# v1.net
KiCad netlist of a schematic drawn in EAGLE
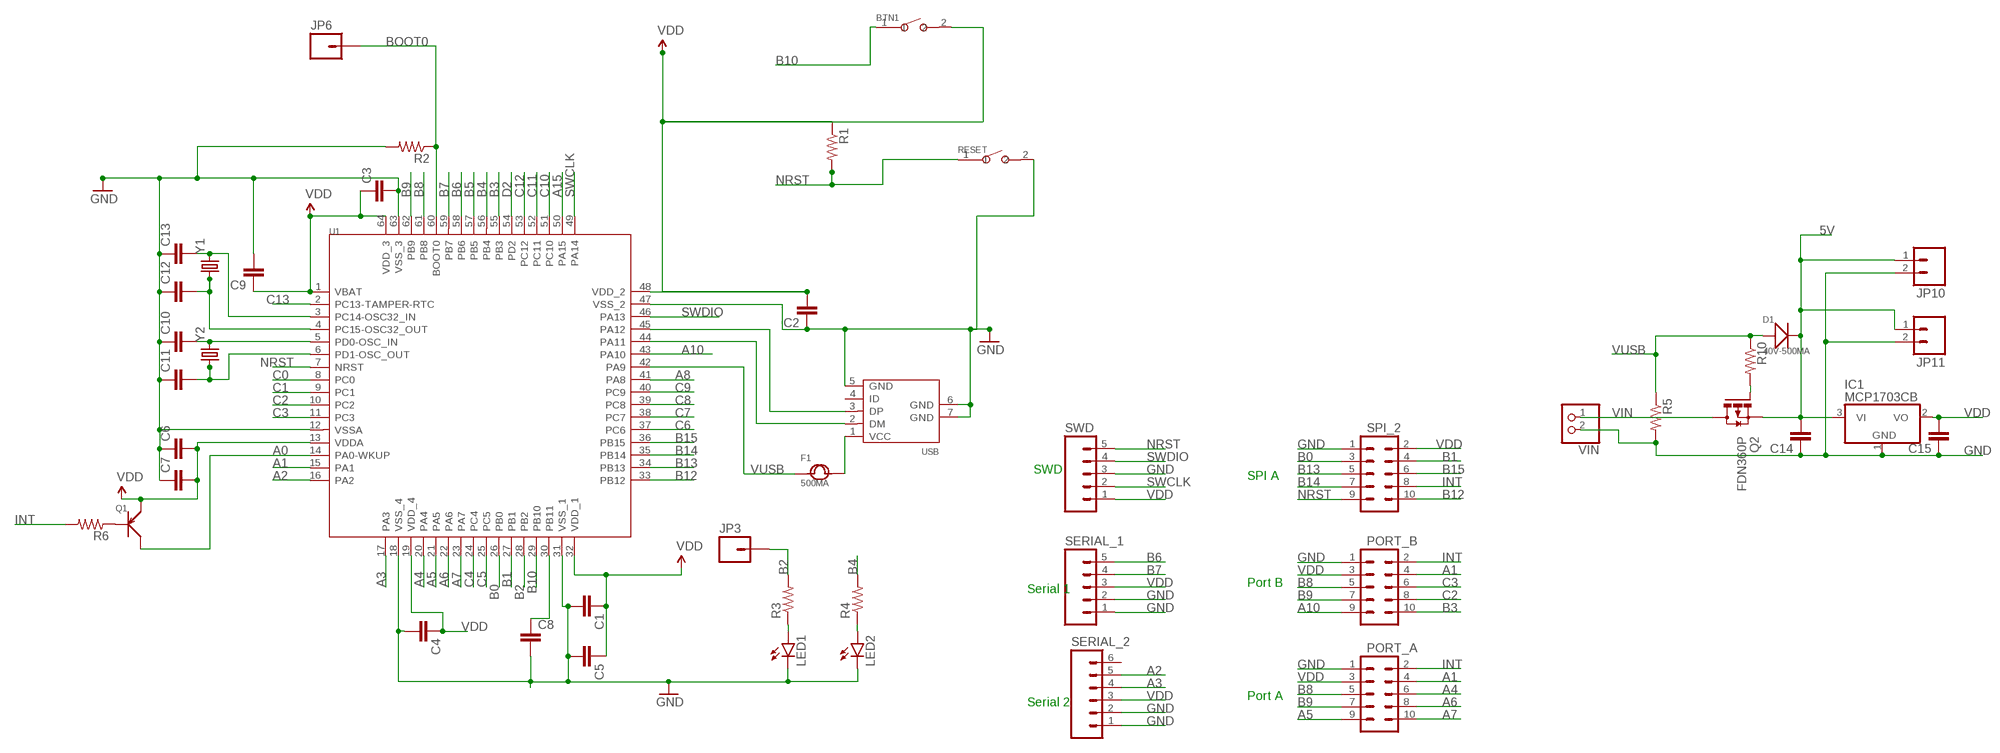
[diagram p0: schematic, sheet 1]

(export (version "E")
  (design (tool "Eeschema 10.0.6"))
  (components
    (comp (ref "BTN1")
      (value "SMD-BUTTON(2P-6.0X3.0X2.5MM)-DHT-1163S")
      (footprint "eagle-import:SW2-4.0-6.0X3.0X2.5MM")
      (libsource (lib "eagle-import") (part "SMD-BUTTON(2P-6.0X3.0X2.5MM)-DHT-1163S"))
    )
    (comp (ref "C1")
      (value "CAP0805")
      (footprint "eagle-import:0805")
      (libsource (lib "eagle-import") (part "CAP0805"))
    )
    (comp (ref "C2")
      (value "CAP0805")
      (footprint "eagle-import:0805")
      (libsource (lib "eagle-import") (part "CAP0805"))
    )
    (comp (ref "C3")
      (value "CAP0805")
      (footprint "eagle-import:0805")
      (libsource (lib "eagle-import") (part "CAP0805"))
    )
    (comp (ref "C4")
      (value "CAP0805")
      (footprint "eagle-import:0805")
      (libsource (lib "eagle-import") (part "CAP0805"))
    )
    (comp (ref "C5")
      (value "CAP0805")
      (footprint "eagle-import:0805")
      (libsource (lib "eagle-import") (part "CAP0805"))
    )
    (comp (ref "C6")
      (value "CAP0805")
      (footprint "eagle-import:0805")
      (libsource (lib "eagle-import") (part "CAP0805"))
    )
    (comp (ref "C7")
      (value "CAP0805")
      (footprint "eagle-import:0805")
      (libsource (lib "eagle-import") (part "CAP0805"))
    )
    (comp (ref "C8")
      (value "CAP0805")
      (footprint "eagle-import:0805")
      (libsource (lib "eagle-import") (part "CAP0805"))
    )
    (comp (ref "C9")
      (value "CAP0805")
      (footprint "eagle-import:0805")
      (libsource (lib "eagle-import") (part "CAP0805"))
    )
    (comp (ref "C10")
      (value "CAP0805")
      (footprint "eagle-import:0805")
      (libsource (lib "eagle-import") (part "CAP0805"))
    )
    (comp (ref "C11")
      (value "CAP0805")
      (footprint "eagle-import:0805")
      (libsource (lib "eagle-import") (part "CAP0805"))
    )
    (comp (ref "C12")
      (value "CAP0805")
      (footprint "eagle-import:0805")
      (libsource (lib "eagle-import") (part "CAP0805"))
    )
    (comp (ref "C13")
      (value "CAP0805")
      (footprint "eagle-import:0805")
      (libsource (lib "eagle-import") (part "CAP0805"))
    )
    (comp (ref "C14")
      (value "CAP0805")
      (footprint "eagle-import:0805")
      (libsource (lib "eagle-import") (part "CAP0805"))
    )
    (comp (ref "C15")
      (value "CAP0805")
      (footprint "eagle-import:0805")
      (libsource (lib "eagle-import") (part "CAP0805"))
    )
    (comp (ref "D1")
      (value "40V-500MA")
      (footprint "eagle-import:SOD-123")
      (fields (field (name "MPN") "B0540W"))
      (libsource (lib "eagle-import") (part "SMD-DIODE-SCHOTTKY-40V-500MA(SOD-123)"))
    )
    (comp (ref "F1")
      (value "500MA")
      (footprint "eagle-import:F1206")
      (libsource (lib "eagle-import") (part "SMD-PPTC-500MA(1206)"))
    )
    (comp (ref "IC1")
      (value "MCP1703CB")
      (footprint "eagle-import:SOT23")
      (libsource (lib "eagle-import") (part "MCP1703CB"))
    )
    (comp (ref "JP3")
      (value "M01NOSILK-KIT")
      (footprint "eagle-import:1X01NS-KIT")
      (libsource (lib "eagle-import") (part "M01NOSILK-KIT"))
    )
    (comp (ref "JP6")
      (value "M01NOSILK-KIT")
      (footprint "eagle-import:1X01NS-KIT")
      (libsource (lib "eagle-import") (part "M01NOSILK-KIT"))
    )
    (comp (ref "JP10")
      (value "M02PTH")
      (footprint "eagle-import:1X02")
      (libsource (lib "eagle-import") (part "M02PTH"))
    )
    (comp (ref "JP11")
      (value "M02PTH")
      (footprint "eagle-import:1X02")
      (libsource (lib "eagle-import") (part "M02PTH"))
    )
    (comp (ref "LED1")
      (value "LED1206")
      (footprint "eagle-import:LED-1206")
      (libsource (lib "eagle-import") (part "LED1206"))
    )
    (comp (ref "LED2")
      (value "LED1206")
      (footprint "eagle-import:LED-1206")
      (libsource (lib "eagle-import") (part "LED1206"))
    )
    (comp (ref "PORT_A")
      (value "M05X2PTH")
      (footprint "eagle-import:AVR_ICSP")
      (libsource (lib "eagle-import") (part "M05X2PTH"))
    )
    (comp (ref "PORT_B")
      (value "M05X2PTH")
      (footprint "eagle-import:AVR_ICSP")
      (libsource (lib "eagle-import") (part "M05X2PTH"))
    )
    (comp (ref "Q1")
      (value "SMD-TRANSISTORS-PNP-25V-500MA(SOT-23)")
      (footprint "eagle-import:SOT-23")
      (fields (field (name "MPN") "S8550"))
      (libsource (lib "eagle-import") (part "SMD-TRANSISTORS-PNP-25V-500MA(SOT-23)"))
    )
    (comp (ref "Q2")
      (value "FDN360P")
      (footprint "eagle-import:SUPER-SOT3")
      (libsource (lib "eagle-import") (part "FDN360P"))
    )
    (comp (ref "R1")
      (value "RESISTOR0805-RES")
      (footprint "eagle-import:0805")
      (libsource (lib "eagle-import") (part "RESISTOR0805-RES"))
    )
    (comp (ref "R2")
      (value "RESISTOR0805-RES")
      (footprint "eagle-import:0805")
      (libsource (lib "eagle-import") (part "RESISTOR0805-RES"))
    )
    (comp (ref "R3")
      (value "RESISTOR0805-RES")
      (footprint "eagle-import:0805")
      (libsource (lib "eagle-import") (part "RESISTOR0805-RES"))
    )
    (comp (ref "R4")
      (value "RESISTOR0805-RES")
      (footprint "eagle-import:0805")
      (libsource (lib "eagle-import") (part "RESISTOR0805-RES"))
    )
    (comp (ref "R5")
      (value "RESISTOR0805-RES")
      (footprint "eagle-import:0805")
      (libsource (lib "eagle-import") (part "RESISTOR0805-RES"))
    )
    (comp (ref "R6")
      (value "RESISTOR0805-RES")
      (footprint "eagle-import:0805")
      (libsource (lib "eagle-import") (part "RESISTOR0805-RES"))
    )
    (comp (ref "R10")
      (value "RESISTOR0805-RES")
      (footprint "eagle-import:0805")
      (libsource (lib "eagle-import") (part "RESISTOR0805-RES"))
    )
    (comp (ref "RESET")
      (value "SMD-BUTTON(2P-6.0X3.0X2.5MM)-DHT-1163S")
      (footprint "eagle-import:SW2-4.0-6.0X3.0X2.5MM")
      (libsource (lib "eagle-import") (part "SMD-BUTTON(2P-6.0X3.0X2.5MM)-DHT-1163S"))
    )
    (comp (ref "SERIAL_1")
      (value "M051.27MM")
      (footprint "eagle-import:1X05-1.27MM")
      (libsource (lib "eagle-import") (part "M051.27MM"))
    )
    (comp (ref "SERIAL_2")
      (value "M06SILK_FEMALE_PTH")
      (footprint "eagle-import:1X06")
      (libsource (lib "eagle-import") (part "M06SILK_FEMALE_PTH"))
    )
    (comp (ref "SPI_2")
      (value "M05X2PTH")
      (footprint "eagle-import:AVR_ICSP")
      (libsource (lib "eagle-import") (part "M05X2PTH"))
    )
    (comp (ref "SWD")
      (value "M051.27MM")
      (footprint "eagle-import:1X05-1.27MM")
      (libsource (lib "eagle-import") (part "M051.27MM"))
    )
    (comp (ref "U1")
      (value "MCU-STM32F401RBT6(LQFP64)")
      (footprint "eagle-import:LQFP64-0.5-10X10MM")
      (fields (field (name "MPN") "STM32F401RBT6"))
      (libsource (lib "eagle-import") (part "MCU-STM32F401RBT6(LQFP64)"))
    )
    (comp (ref "USB")
      (value "MICRO-USB-SMD-TYPE-AB-R/A(ST-USB-001L)")
      (footprint "eagle-import:MICRO-USB5+2P-SMD-0.65")
      (fields (field (name "MPN") "ST-USB-001L"))
      (libsource (lib "eagle-import") (part "MICRO-USB-SMD-TYPE-AB-R/A(ST-USB-001L)"))
    )
    (comp (ref "VIN")
      (value "JST_2PIN-SMT-RA")
      (footprint "eagle-import:JST-PH-2-SMT-RA")
      (libsource (lib "eagle-import") (part "JST_2PIN-SMT-RA"))
    )
    (comp (ref "Y1")
      (value "CRYSTAL5X3")
      (footprint "eagle-import:CRYSTAL-SMD-5X3")
      (libsource (lib "eagle-import") (part "CRYSTAL5X3"))
    )
    (comp (ref "Y2")
      (value "CRYSTAL5X3")
      (footprint "eagle-import:CRYSTAL-SMD-5X3")
      (libsource (lib "eagle-import") (part "CRYSTAL5X3"))
    )
  )
  (nets
    (net (code "1") (name "/5V") (class "Default")
      (node (ref "C14") (pin "2") (pinfunction "2_2") (pintype "passive"))
      (node (ref "D1") (pin "-") (pinfunction "-_-") (pintype "passive"))
      (node (ref "IC1") (pin "3") (pinfunction "VI_3") (pintype "input"))
      (node (ref "JP10") (pin "1") (pinfunction "1_1") (pintype "passive"))
      (node (ref "JP11") (pin "1") (pinfunction "1_1") (pintype "passive"))
      (node (ref "Q2") (pin "2") (pinfunction "S_2") (pintype "passive"))
    )
    (net (code "2") (name "/A0") (class "Default")
      (node (ref "Q1") (pin "3") (pinfunction "C_3") (pintype "passive"))
      (node (ref "U1") (pin "14") (pinfunction "PA0-WKUP_14") (pintype "bidirectional"))
    )
    (net (code "3") (name "/A1") (class "Default")
      (node (ref "PORT_A") (pin "4") (pinfunction "4_4") (pintype "passive"))
      (node (ref "PORT_B") (pin "4") (pinfunction "4_4") (pintype "passive"))
      (node (ref "U1") (pin "15") (pinfunction "PA1_15") (pintype "bidirectional"))
    )
    (net (code "4") (name "/A2") (class "Default")
      (node (ref "SERIAL_2") (pin "5") (pinfunction "5_5") (pintype "passive"))
      (node (ref "U1") (pin "16") (pinfunction "PA2_16") (pintype "bidirectional"))
    )
    (net (code "5") (name "/A3") (class "Default")
      (node (ref "SERIAL_2") (pin "4") (pinfunction "4_4") (pintype "passive"))
      (node (ref "U1") (pin "17") (pinfunction "PA3_17") (pintype "bidirectional"))
    )
    (net (code "6") (name "/A4") (class "Default")
      (node (ref "PORT_A") (pin "6") (pinfunction "6_6") (pintype "passive"))
      (node (ref "U1") (pin "20") (pinfunction "PA4_20") (pintype "bidirectional"))
    )
    (net (code "7") (name "/A5") (class "Default")
      (node (ref "PORT_A") (pin "9") (pinfunction "9_9") (pintype "passive"))
      (node (ref "U1") (pin "21") (pinfunction "PA5_21") (pintype "bidirectional"))
    )
    (net (code "8") (name "/A6") (class "Default")
      (node (ref "PORT_A") (pin "8") (pinfunction "8_8") (pintype "passive"))
      (node (ref "U1") (pin "22") (pinfunction "PA6_22") (pintype "bidirectional"))
    )
    (net (code "9") (name "/A7") (class "Default")
      (node (ref "PORT_A") (pin "10") (pinfunction "10_10") (pintype "passive"))
      (node (ref "U1") (pin "23") (pinfunction "PA7_23") (pintype "bidirectional"))
    )
    (net (code "10") (name "/A8") (class "Default")
      (node (ref "U1") (pin "41") (pinfunction "PA8_41") (pintype "bidirectional"))
    )
    (net (code "11") (name "/A10") (class "Default")
      (node (ref "PORT_B") (pin "9") (pinfunction "9_9") (pintype "passive"))
      (node (ref "U1") (pin "43") (pinfunction "PA10_43") (pintype "bidirectional"))
    )
    (net (code "12") (name "/A15") (class "Default")
      (node (ref "U1") (pin "50") (pinfunction "PA15_50") (pintype "bidirectional"))
    )
    (net (code "13") (name "/B0") (class "Default")
      (node (ref "SPI_2") (pin "3") (pinfunction "3_3") (pintype "passive"))
      (node (ref "U1") (pin "26") (pinfunction "PB0_26") (pintype "bidirectional"))
    )
    (net (code "14") (name "/B1") (class "Default")
      (node (ref "SPI_2") (pin "4") (pinfunction "4_4") (pintype "passive"))
      (node (ref "U1") (pin "27") (pinfunction "PB1_27") (pintype "bidirectional"))
    )
    (net (code "15") (name "/B2") (class "Default")
      (node (ref "JP3") (pin "1") (pinfunction "1_1") (pintype "passive"))
      (node (ref "R3") (pin "2") (pinfunction "2_2") (pintype "passive"))
      (node (ref "U1") (pin "28") (pinfunction "PB2_28") (pintype "bidirectional"))
    )
    (net (code "16") (name "/B3") (class "Default")
      (node (ref "PORT_B") (pin "10") (pinfunction "10_10") (pintype "passive"))
      (node (ref "U1") (pin "55") (pinfunction "PB3_55") (pintype "bidirectional"))
    )
    (net (code "17") (name "/B4") (class "Default")
      (node (ref "R4") (pin "2") (pinfunction "2_2") (pintype "passive"))
      (node (ref "U1") (pin "56") (pinfunction "PB4_56") (pintype "bidirectional"))
    )
    (net (code "18") (name "/B5") (class "Default")
      (node (ref "U1") (pin "57") (pinfunction "PB5_57") (pintype "bidirectional"))
    )
    (net (code "19") (name "/B6") (class "Default")
      (node (ref "SERIAL_1") (pin "5") (pinfunction "5_5") (pintype "passive"))
      (node (ref "U1") (pin "58") (pinfunction "PB6_58") (pintype "bidirectional"))
    )
    (net (code "20") (name "/B7") (class "Default")
      (node (ref "SERIAL_1") (pin "4") (pinfunction "4_4") (pintype "passive"))
      (node (ref "U1") (pin "59") (pinfunction "PB7_59") (pintype "bidirectional"))
    )
    (net (code "21") (name "/B8") (class "Default")
      (node (ref "PORT_A") (pin "5") (pinfunction "5_5") (pintype "passive"))
      (node (ref "PORT_B") (pin "5") (pinfunction "5_5") (pintype "passive"))
      (node (ref "U1") (pin "61") (pinfunction "PB8_61") (pintype "bidirectional"))
    )
    (net (code "22") (name "/B9") (class "Default")
      (node (ref "PORT_A") (pin "7") (pinfunction "7_7") (pintype "passive"))
      (node (ref "PORT_B") (pin "7") (pinfunction "7_7") (pintype "passive"))
      (node (ref "U1") (pin "62") (pinfunction "PB9_62") (pintype "bidirectional"))
    )
    (net (code "23") (name "/B10") (class "Default")
      (node (ref "BTN1") (pin "1") (pinfunction "1_1") (pintype "bidirectional"))
      (node (ref "U1") (pin "29") (pinfunction "PB10_29") (pintype "bidirectional"))
    )
    (net (code "24") (name "/B12") (class "Default")
      (node (ref "SPI_2") (pin "10") (pinfunction "10_10") (pintype "passive"))
      (node (ref "U1") (pin "33") (pinfunction "PB12_33") (pintype "bidirectional"))
    )
    (net (code "25") (name "/B13") (class "Default")
      (node (ref "SPI_2") (pin "5") (pinfunction "5_5") (pintype "passive"))
      (node (ref "U1") (pin "34") (pinfunction "PB13_34") (pintype "bidirectional"))
    )
    (net (code "26") (name "/B14") (class "Default")
      (node (ref "SPI_2") (pin "7") (pinfunction "7_7") (pintype "passive"))
      (node (ref "U1") (pin "35") (pinfunction "PB14_35") (pintype "bidirectional"))
    )
    (net (code "27") (name "/B15") (class "Default")
      (node (ref "SPI_2") (pin "6") (pinfunction "6_6") (pintype "passive"))
      (node (ref "U1") (pin "36") (pinfunction "PB15_36") (pintype "bidirectional"))
    )
    (net (code "28") (name "/BOOT0") (class "Default")
      (node (ref "JP6") (pin "1") (pinfunction "1_1") (pintype "passive"))
      (node (ref "R2") (pin "1") (pinfunction "1_1") (pintype "passive"))
      (node (ref "U1") (pin "60") (pinfunction "BOOT0_60") (pintype "bidirectional"))
    )
    (net (code "29") (name "/C0") (class "Default")
      (node (ref "U1") (pin "8") (pinfunction "PC0_8") (pintype "bidirectional"))
    )
    (net (code "30") (name "/C1") (class "Default")
      (node (ref "U1") (pin "9") (pinfunction "PC1_9") (pintype "bidirectional"))
    )
    (net (code "31") (name "/C2") (class "Default")
      (node (ref "PORT_B") (pin "8") (pinfunction "8_8") (pintype "passive"))
      (node (ref "U1") (pin "10") (pinfunction "PC2_10") (pintype "bidirectional"))
    )
    (net (code "32") (name "/C3") (class "Default")
      (node (ref "PORT_B") (pin "6") (pinfunction "6_6") (pintype "passive"))
      (node (ref "U1") (pin "11") (pinfunction "PC3_11") (pintype "bidirectional"))
    )
    (net (code "33") (name "/C4") (class "Default")
      (node (ref "U1") (pin "24") (pinfunction "PC4_24") (pintype "bidirectional"))
    )
    (net (code "34") (name "/C5") (class "Default")
      (node (ref "U1") (pin "25") (pinfunction "PC5_25") (pintype "bidirectional"))
    )
    (net (code "35") (name "/C6") (class "Default")
      (node (ref "U1") (pin "37") (pinfunction "PC6_37") (pintype "bidirectional"))
    )
    (net (code "36") (name "/C7") (class "Default")
      (node (ref "U1") (pin "38") (pinfunction "PC7_38") (pintype "bidirectional"))
    )
    (net (code "37") (name "/C8") (class "Default")
      (node (ref "U1") (pin "39") (pinfunction "PC8_39") (pintype "bidirectional"))
    )
    (net (code "38") (name "/C9") (class "Default")
      (node (ref "U1") (pin "40") (pinfunction "PC9_40") (pintype "bidirectional"))
    )
    (net (code "39") (name "/C10") (class "Default")
      (node (ref "U1") (pin "51") (pinfunction "PC10_51") (pintype "bidirectional"))
    )
    (net (code "40") (name "/C11") (class "Default")
      (node (ref "U1") (pin "52") (pinfunction "PC11_52") (pintype "bidirectional"))
    )
    (net (code "41") (name "/C12") (class "Default")
      (node (ref "U1") (pin "53") (pinfunction "PC12_53") (pintype "bidirectional"))
    )
    (net (code "42") (name "/C13") (class "Default")
      (node (ref "U1") (pin "2") (pinfunction "PC13-TAMPER-RTC_2") (pintype "bidirectional"))
    )
    (net (code "43") (name "/D2") (class "Default")
      (node (ref "U1") (pin "54") (pinfunction "PD2_54") (pintype "bidirectional"))
    )
    (net (code "44") (name "/INT") (class "Default")
      (node (ref "PORT_A") (pin "2") (pinfunction "2_2") (pintype "passive"))
      (node (ref "PORT_B") (pin "2") (pinfunction "2_2") (pintype "passive"))
      (node (ref "R6") (pin "2") (pinfunction "2_2") (pintype "passive"))
      (node (ref "SPI_2") (pin "8") (pinfunction "8_8") (pintype "passive"))
    )
    (net (code "45") (name "/NRST") (class "Default")
      (node (ref "R1") (pin "2") (pinfunction "2_2") (pintype "passive"))
      (node (ref "RESET") (pin "1") (pinfunction "1_1") (pintype "bidirectional"))
      (node (ref "SPI_2") (pin "9") (pinfunction "9_9") (pintype "passive"))
      (node (ref "SWD") (pin "5") (pinfunction "5_5") (pintype "passive"))
      (node (ref "U1") (pin "7") (pinfunction "NRST_7") (pintype "bidirectional"))
    )
    (net (code "46") (name "/SWCLK") (class "Default")
      (node (ref "SWD") (pin "2") (pinfunction "2_2") (pintype "passive"))
      (node (ref "U1") (pin "49") (pinfunction "PA14_49") (pintype "bidirectional"))
    )
    (net (code "47") (name "/SWDIO") (class "Default")
      (node (ref "SWD") (pin "4") (pinfunction "4_4") (pintype "passive"))
      (node (ref "U1") (pin "46") (pinfunction "PA13_46") (pintype "bidirectional"))
    )
    (net (code "48") (name "/VIN") (class "Default")
      (node (ref "Q2") (pin "3") (pinfunction "D_3") (pintype "passive"))
      (node (ref "VIN") (pin "1") (pinfunction "2_1") (pintype "passive"))
    )
    (net (code "49") (name "/VUSB") (class "Default")
      (node (ref "D1") (pin "+") (pinfunction "+_+") (pintype "passive"))
      (node (ref "F1") (pin "1") (pinfunction "1_1") (pintype "bidirectional"))
      (node (ref "R10") (pin "1") (pinfunction "1_1") (pintype "passive"))
      (node (ref "R5") (pin "1") (pinfunction "1_1") (pintype "passive"))
      (node (ref "U1") (pin "42") (pinfunction "PA9_42") (pintype "bidirectional"))
    )
    (net (code "50") (name "GND") (class "Default")
      (node (ref "C1") (pin "2") (pinfunction "2_2") (pintype "passive"))
      (node (ref "C10") (pin "1") (pinfunction "1_1") (pintype "passive"))
      (node (ref "C11") (pin "1") (pinfunction "1_1") (pintype "passive"))
      (node (ref "C12") (pin "1") (pinfunction "1_1") (pintype "passive"))
      (node (ref "C13") (pin "1") (pinfunction "1_1") (pintype "passive"))
      (node (ref "C14") (pin "1") (pinfunction "1_1") (pintype "passive"))
      (node (ref "C15") (pin "1") (pinfunction "1_1") (pintype "passive"))
      (node (ref "C2") (pin "1") (pinfunction "1_1") (pintype "passive"))
      (node (ref "C3") (pin "2") (pinfunction "2_2") (pintype "passive"))
      (node (ref "C4") (pin "2") (pinfunction "2_2") (pintype "passive"))
      (node (ref "C5") (pin "2") (pinfunction "2_2") (pintype "passive"))
      (node (ref "C6") (pin "1") (pinfunction "1_1") (pintype "passive"))
      (node (ref "C7") (pin "1") (pinfunction "1_1") (pintype "passive"))
      (node (ref "C8") (pin "2") (pinfunction "2_2") (pintype "passive"))
      (node (ref "C9") (pin "2") (pinfunction "2_2") (pintype "passive"))
      (node (ref "IC1") (pin "1") (pinfunction "GND_1") (pintype "passive"))
      (node (ref "JP10") (pin "2") (pinfunction "2_2") (pintype "passive"))
      (node (ref "JP11") (pin "2") (pinfunction "2_2") (pintype "passive"))
      (node (ref "LED1") (pin "C") (pinfunction "C_C") (pintype "passive"))
      (node (ref "LED2") (pin "C") (pinfunction "C_C") (pintype "passive"))
      (node (ref "PORT_A") (pin "1") (pinfunction "1_1") (pintype "passive"))
      (node (ref "PORT_B") (pin "1") (pinfunction "1_1") (pintype "passive"))
      (node (ref "R2") (pin "2") (pinfunction "2_2") (pintype "passive"))
      (node (ref "R5") (pin "2") (pinfunction "2_2") (pintype "passive"))
      (node (ref "RESET") (pin "2") (pinfunction "2_2") (pintype "bidirectional"))
      (node (ref "SERIAL_1") (pin "1") (pinfunction "1_1") (pintype "passive"))
      (node (ref "SERIAL_1") (pin "2") (pinfunction "2_2") (pintype "passive"))
      (node (ref "SERIAL_2") (pin "1") (pinfunction "1_1") (pintype "passive"))
      (node (ref "SERIAL_2") (pin "2") (pinfunction "2_2") (pintype "passive"))
      (node (ref "SPI_2") (pin "1") (pinfunction "1_1") (pintype "passive"))
      (node (ref "SWD") (pin "3") (pinfunction "3_3") (pintype "passive"))
      (node (ref "U1") (pin "12") (pinfunction "VSSA_12") (pintype "bidirectional"))
      (node (ref "U1") (pin "18") (pinfunction "VSS_4_18") (pintype "bidirectional"))
      (node (ref "U1") (pin "31") (pinfunction "VSS_1_31") (pintype "bidirectional"))
      (node (ref "U1") (pin "47") (pinfunction "VSS_2_47") (pintype "bidirectional"))
      (node (ref "U1") (pin "63") (pinfunction "VSS_3_63") (pintype "bidirectional"))
      (node (ref "USB") (pin "5") (pinfunction "GND_5") (pintype "bidirectional"))
      (node (ref "USB") (pin "6") (pinfunction "GND_6") (pintype "bidirectional"))
      (node (ref "USB") (pin "7") (pinfunction "GND_7") (pintype "bidirectional"))
      (node (ref "VIN") (pin "2") (pinfunction "1_2") (pintype "passive"))
    )
    (net (code "51") (name "Net-(LED1-PadA)") (class "Default")
      (node (ref "LED1") (pin "A") (pinfunction "A_A") (pintype "passive"))
      (node (ref "R3") (pin "1") (pinfunction "1_1") (pintype "passive"))
    )
    (net (code "52") (name "Net-(LED2-PadA)") (class "Default")
      (node (ref "LED2") (pin "A") (pinfunction "A_A") (pintype "passive"))
      (node (ref "R4") (pin "1") (pinfunction "1_1") (pintype "passive"))
    )
    (net (code "53") (name "Net-(Q1-B)") (class "Default")
      (node (ref "Q1") (pin "1") (pinfunction "B_1") (pintype "passive"))
      (node (ref "R6") (pin "1") (pinfunction "1_1") (pintype "passive"))
    )
    (net (code "54") (name "Net-(Q2-G)") (class "Default")
      (node (ref "Q2") (pin "1") (pinfunction "G_1") (pintype "passive"))
      (node (ref "R10") (pin "2") (pinfunction "2_2") (pintype "passive"))
    )
    (net (code "55") (name "Net-(U1-PA11)") (class "Default")
      (node (ref "U1") (pin "44") (pinfunction "PA11_44") (pintype "bidirectional"))
      (node (ref "USB") (pin "2") (pinfunction "DM_2") (pintype "bidirectional"))
    )
    (net (code "56") (name "Net-(U1-PA12)") (class "Default")
      (node (ref "U1") (pin "45") (pinfunction "PA12_45") (pintype "bidirectional"))
      (node (ref "USB") (pin "3") (pinfunction "DP_3") (pintype "bidirectional"))
    )
    (net (code "57") (name "Net-(U1-PB11)") (class "Default")
      (node (ref "C8") (pin "1") (pinfunction "1_1") (pintype "passive"))
      (node (ref "U1") (pin "30") (pinfunction "PB11_30") (pintype "bidirectional"))
    )
    (net (code "58") (name "Net-(U1-PC14-OSC32_IN)") (class "Default")
      (node (ref "C13") (pin "2") (pinfunction "2_2") (pintype "passive"))
      (node (ref "U1") (pin "3") (pinfunction "PC14-OSC32_IN_3") (pintype "bidirectional"))
      (node (ref "Y1") (pin "3") (pinfunction "2_3") (pintype "passive"))
    )
    (net (code "59") (name "Net-(U1-PC15-OSC32_OUT)") (class "Default")
      (node (ref "C12") (pin "2") (pinfunction "2_2") (pintype "passive"))
      (node (ref "U1") (pin "4") (pinfunction "PC15-OSC32_OUT_4") (pintype "bidirectional"))
      (node (ref "Y1") (pin "1") (pinfunction "1_1") (pintype "passive"))
    )
    (net (code "60") (name "Net-(U1-PD0-OSC_IN)") (class "Default")
      (node (ref "C10") (pin "2") (pinfunction "2_2") (pintype "passive"))
      (node (ref "U1") (pin "5") (pinfunction "PD0-OSC_IN_5") (pintype "bidirectional"))
      (node (ref "Y2") (pin "3") (pinfunction "2_3") (pintype "passive"))
    )
    (net (code "61") (name "Net-(U1-PD1-OSC_OUT)") (class "Default")
      (node (ref "C11") (pin "2") (pinfunction "2_2") (pintype "passive"))
      (node (ref "U1") (pin "6") (pinfunction "PD1-OSC_OUT_6") (pintype "bidirectional"))
      (node (ref "Y2") (pin "1") (pinfunction "1_1") (pintype "passive"))
    )
    (net (code "62") (name "Net-(USB-VCC)") (class "Default")
      (node (ref "F1") (pin "2") (pinfunction "2_2") (pintype "bidirectional"))
      (node (ref "USB") (pin "1") (pinfunction "VCC_1") (pintype "bidirectional"))
    )
    (net (code "63") (name "VDD") (class "Default")
      (node (ref "BTN1") (pin "2") (pinfunction "2_2") (pintype "bidirectional"))
      (node (ref "C1") (pin "1") (pinfunction "1_1") (pintype "passive"))
      (node (ref "C15") (pin "2") (pinfunction "2_2") (pintype "passive"))
      (node (ref "C2") (pin "2") (pinfunction "2_2") (pintype "passive"))
      (node (ref "C3") (pin "1") (pinfunction "1_1") (pintype "passive"))
      (node (ref "C4") (pin "1") (pinfunction "1_1") (pintype "passive"))
      (node (ref "C5") (pin "1") (pinfunction "1_1") (pintype "passive"))
      (node (ref "C6") (pin "2") (pinfunction "2_2") (pintype "passive"))
      (node (ref "C7") (pin "2") (pinfunction "2_2") (pintype "passive"))
      (node (ref "C9") (pin "1") (pinfunction "1_1") (pintype "passive"))
      (node (ref "IC1") (pin "2") (pinfunction "VO_2") (pintype "passive"))
      (node (ref "PORT_A") (pin "3") (pinfunction "3_3") (pintype "passive"))
      (node (ref "PORT_B") (pin "3") (pinfunction "3_3") (pintype "passive"))
      (node (ref "Q1") (pin "2") (pinfunction "E_2") (pintype "passive"))
      (node (ref "R1") (pin "1") (pinfunction "1_1") (pintype "passive"))
      (node (ref "SERIAL_1") (pin "3") (pinfunction "3_3") (pintype "passive"))
      (node (ref "SERIAL_2") (pin "3") (pinfunction "3_3") (pintype "passive"))
      (node (ref "SPI_2") (pin "2") (pinfunction "2_2") (pintype "passive"))
      (node (ref "SWD") (pin "1") (pinfunction "1_1") (pintype "passive"))
      (node (ref "U1") (pin "1") (pinfunction "VBAT_1") (pintype "bidirectional"))
      (node (ref "U1") (pin "13") (pinfunction "VDDA_13") (pintype "bidirectional"))
      (node (ref "U1") (pin "19") (pinfunction "VDD_4_19") (pintype "bidirectional"))
      (node (ref "U1") (pin "32") (pinfunction "VDD_1_32") (pintype "bidirectional"))
      (node (ref "U1") (pin "48") (pinfunction "VDD_2_48") (pintype "bidirectional"))
      (node (ref "U1") (pin "64") (pinfunction "VDD_3_64") (pintype "bidirectional"))
    )
    (net (code "64") (name "unconnected-(SERIAL_2-Pad6)") (class "Default")
      (node (ref "SERIAL_2") (pin "6") (pinfunction "6_6") (pintype "passive"))
    )
    (net (code "65") (name "unconnected-(USB-ID-Pad4)") (class "Default")
      (node (ref "USB") (pin "4") (pinfunction "ID_4") (pintype "bidirectional"))
    )
  )
)
